# H19R1_Backend.net
KiCad netlist of a schematic drawn in Altium Designer
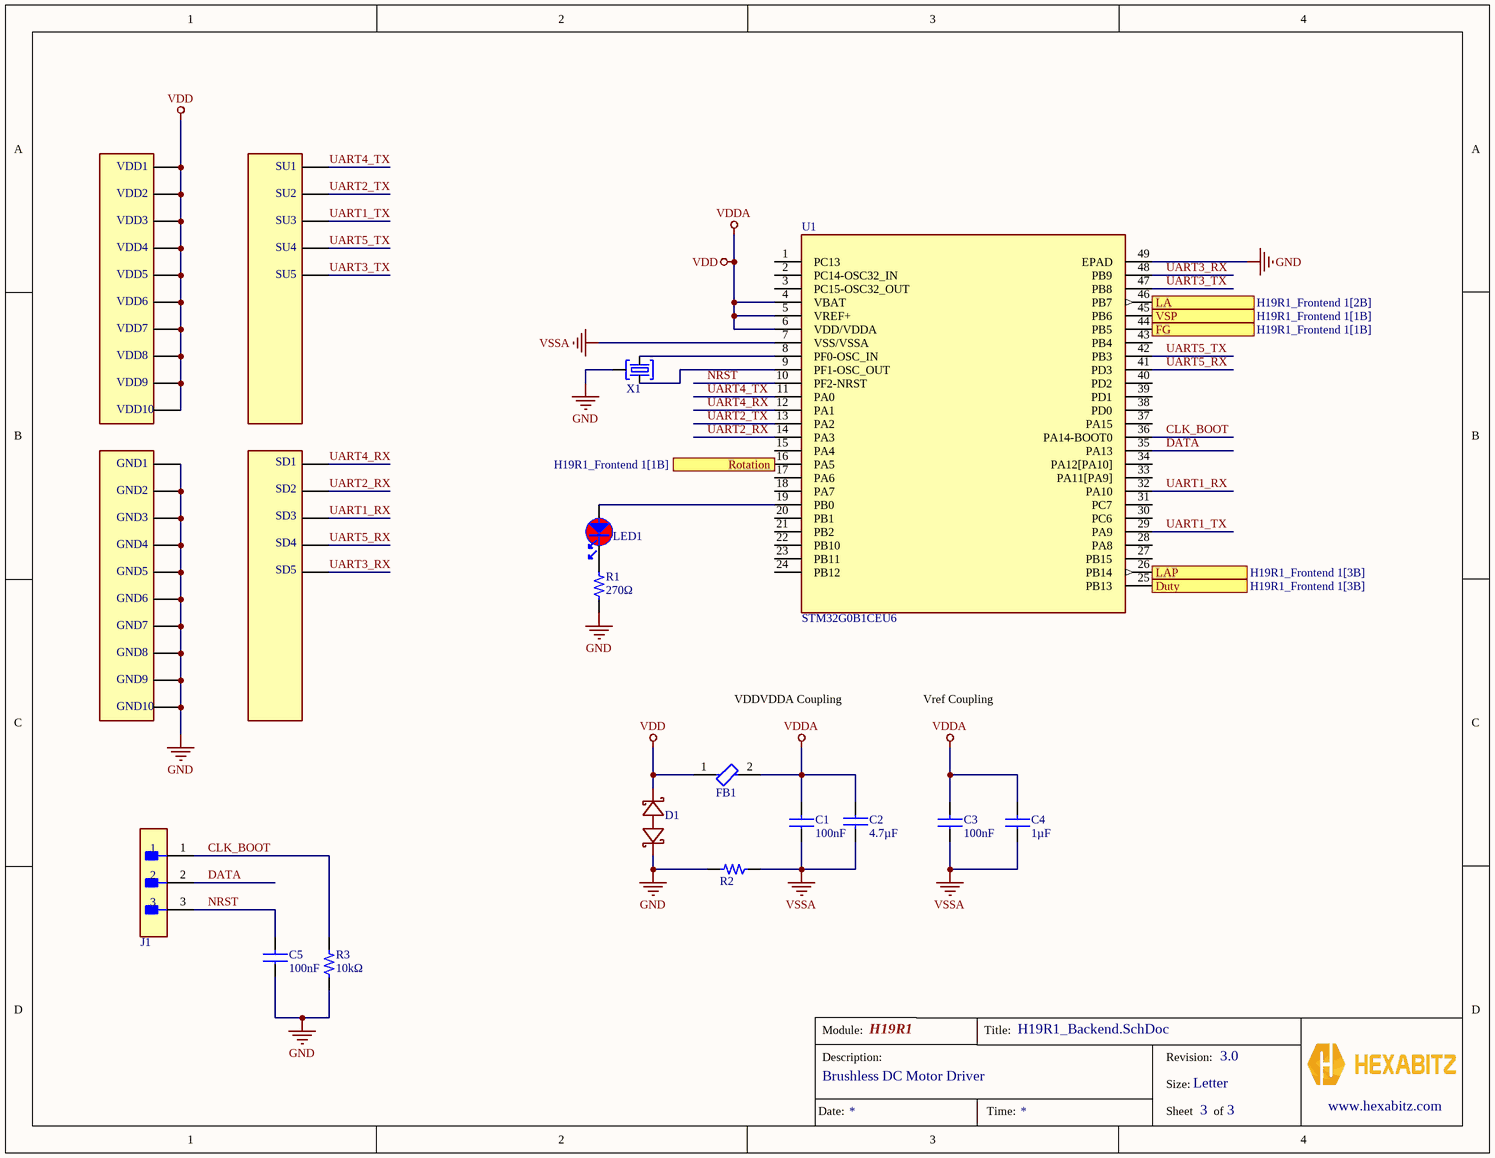
[diagram p0: H19R1_Backend.SchDoc]

(export (version "E")
  (design (tool "Eeschema 10.0.6"))
  (components
    (comp (ref "C1")
      (value "100nF")
      (footprint "C0603")
      (fields
        (field (name "MANUFACTURER") "Samsung Electro-Mechanics")
        (field (name "MANUFACTURER PART NUMBER") "CL10B104KA8NNNC")
        (field (name "TOLERANCE") "10%")
      )
      (libsource (lib "Hexabitz Altium Library") (part "generic Capacitor"))
    )
    (comp (ref "C2")
      (value "4.7µF")
      (footprint "C0805")
      (fields
        (field (name "MANUFACTURER") "Samsung Electro-Mechanics")
        (field (name "MANUFACTURER PART NUMBER") "CL21X475KAQNNNE")
        (field (name "TOLERANCE") "10%")
      )
      (libsource (lib "Hexabitz Altium Library") (part "generic Capacitor"))
    )
    (comp (ref "C3")
      (value "100nF")
      (footprint "C0603")
      (fields
        (field (name "MANUFACTURER") "Samsung Electro-Mechanics")
        (field (name "MANUFACTURER PART NUMBER") "CL10B104KA8NNNC")
        (field (name "TOLERANCE") "10%")
      )
      (libsource (lib "Hexabitz Altium Library") (part "generic Capacitor"))
    )
    (comp (ref "C4")
      (value "1µF")
      (footprint "C0805")
      (description "Ceramic Capacitor, Ceramic, 16V, 10% +Tol, 10% -Tol, X7R, 15% TC, 1uF, Surface Mount, 0805")
      (fields
        (field (name "MANUFACTURER") "Yageo Group")
        (field (name "MANUFACTURER PART NUMBER") "CC0805KKX7R7BB105")
      )
      (libsource (lib "Hexabitz Altium Library") (part "generic Capacitor"))
    )
    (comp (ref "C5")
      (value "100nF")
      (footprint "C0603")
      (fields
        (field (name "MANUFACTURER") "Samsung Electro-Mechanics")
        (field (name "MANUFACTURER PART NUMBER") "CL10B104KA8NNNC")
        (field (name "TOLERANCE") "10%")
      )
      (libsource (lib "Hexabitz Altium Library") (part "generic Capacitor"))
    )
    (comp (ref "D1")
      (value "CDSOD323-T03SC")
      (footprint "SOD2513X114N")
      (description "A 3V, 350W, bi-directional, standard capacitance, SOD323 pkg TVS Diode ¦ Bourns CDSOD323-T03SC")
      (fields (field (name "MANUFACTURER") "Bourns"))
      (libsource (lib "Hexabitz Altium Library") (part "CDSOD323-T03SC"))
    )
    (comp (ref "FB1")
      (value "MMZ1608Y300B")
      (footprint "FP-MMZ1608-0_8-MFG")
      (description "Ferrite Beads 0603 30ohms 1500mA Signal Line AEC-Q200")
      (fields
        (field (name "MANUFACTURER") "TDK")
        (field (name "MANUFACTURER PART NUMBER") "MMZ1608Y300BTD25")
      )
      (libsource (lib "Hexabitz Altium Library") (part "MMZ1608Y300B"))
    )
    (comp (ref "GND1")
      (value "HEXABIT_UART_PORT")
      (footprint "HEXABIT_POWER_PORT_D")
      (libsource (lib "hexabitz_connectors.Library") (part "HEXABIT_POWER_PORT_D"))
    )
    (comp (ref "GND2")
      (value "HEXABIT_UART_PORT")
      (footprint "HEXABIT_POWER_PORT_D")
      (libsource (lib "hexabitz_connectors.Library") (part "HEXABIT_POWER_PORT_D"))
    )
    (comp (ref "GND3")
      (value "HEXABIT_UART_PORT")
      (footprint "HEXABIT_POWER_PORT_D_300R")
      (libsource (lib "hexabitz_connectors.Library") (part "HEXABIT_POWER_PORT_D_300R"))
    )
    (comp (ref "GND4")
      (value "HEXABIT_UART_PORT")
      (footprint "HEXABIT_POWER_PORT_D")
      (libsource (lib "hexabitz_connectors.Library") (part "HEXABIT_POWER_PORT_D"))
    )
    (comp (ref "GND5")
      (value "HEXABIT_UART_PORT")
      (footprint "HEXABIT_POWER_PORT_D")
      (libsource (lib "hexabitz_connectors.Library") (part "HEXABIT_POWER_PORT_D"))
    )
    (comp (ref "GND6")
      (value "HEXABIT_UART_PORT")
      (footprint "HEXABIT_POWER_PORT_D")
      (libsource (lib "hexabitz_connectors.Library") (part "HEXABIT_POWER_PORT_D"))
    )
    (comp (ref "GND7")
      (value "HEXABIT_UART_PORT")
      (footprint "HEXABIT_POWER_PORT_D")
      (libsource (lib "hexabitz_connectors.Library") (part "HEXABIT_POWER_PORT_D"))
    )
    (comp (ref "GND8")
      (value "HEXABIT_UART_PORT")
      (footprint "HEXABIT_POWER_PORT_D_300L")
      (libsource (lib "hexabitz_connectors.Library") (part "HEXABIT_POWER_PORT_D_300L"))
    )
    (comp (ref "GND9")
      (value "HEXABIT_UART_PORT")
      (footprint "HEXABIT_POWER_PORT_D")
      (libsource (lib "hexabitz_connectors.Library") (part "HEXABIT_POWER_PORT_D"))
    )
    (comp (ref "GND10")
      (value "HEXABIT_UART_PORT")
      (footprint "HEXABIT_POWER_PORT_D")
      (libsource (lib "hexabitz_connectors.Library") (part "HEXABIT_POWER_PORT_D"))
    )
    (comp (ref "J1")
      (value "TSW-103-14-G-S")
      (footprint "FP-TSW-103-14-G-S-MFG")
      (description "CONN HEADER VERT 3POS 2.54MM")
      (libsource (lib "Altium Content Vault") (part "cd3439d6ef35ae5d9b27ec4fdd3e828"))
    )
    (comp (ref "LED1")
      (value "VLMS1300-GS08")
      (footprint "FP-6_541-5092_01-4-MFG")
      (description "LED Uni-Color Super Red 639nm 2-Pin Chip 0603(1608Metric) T/R")
      (fields (field (name "MANUFACTURER") "Vishay Semiconductors"))
      (libsource (lib "Hexabitz Altium Library") (part "VLMS1300-GS08"))
    )
    (comp (ref "R1")
      (value "270Ω")
      (footprint "R0603")
      (description "Res Thick Film 0603 270 Ohm 5% 0.1W(1/10W) ±200ppm/C Pad SMD Automotive T/R")
      (fields
        (field (name "MANUFACTURER") "Panasonic")
        (field (name "MANUFACTURER PART NUMBER") "ERJ-3GEYJ271V")
      )
      (libsource (lib "") (part "generic Resistor_2"))
    )
    (comp (ref "R2")
      (value "Manufacturer Part Number")
      (footprint "R0603")
      (libsource (lib "Hexabitz Altium Library") (part "generic Resistor"))
    )
    (comp (ref "R3")
      (value "10kΩ")
      (footprint "R0603")
      (description "100mW Thick Film Resistors ±100ppm/℃ ±1% 10kΩ 0603 Chip Resistor - Surface Mount ROHS")
      (fields
        (field (name "MANUFACTURER") "Yageo Group")
        (field (name "MANUFACTURER PART NUMBER") "RC0603FR-0710KL")
      )
      (libsource (lib "") (part "generic Resistor_1"))
    )
    (comp (ref "SD1")
      (value "HEXABIT_UART_PORT")
      (footprint "HEXABIT_UART_PORT_D")
      (libsource (lib "hexabitz_connectors.Library") (part "HEXABIT_UART_PORT_D"))
    )
    (comp (ref "SD2")
      (value "HEXABIT_UART_PORT")
      (footprint "HEXABIT_UART_PORT_D")
      (libsource (lib "hexabitz_connectors.Library") (part "HEXABIT_UART_PORT_D"))
    )
    (comp (ref "SD3")
      (value "HEXABIT_UART_PORT")
      (footprint "HEXABIT_UART_PORT_D")
      (libsource (lib "hexabitz_connectors.Library") (part "HEXABIT_UART_PORT_D"))
    )
    (comp (ref "SD4")
      (value "HEXABIT_UART_PORT")
      (footprint "HEXABIT_UART_PORT_D")
      (libsource (lib "hexabitz_connectors.Library") (part "HEXABIT_UART_PORT_D"))
    )
    (comp (ref "SD5")
      (value "HEXABIT_UART_PORT")
      (footprint "HEXABIT_UART_PORT_D")
      (libsource (lib "hexabitz_connectors.Library") (part "HEXABIT_UART_PORT_D"))
    )
    (comp (ref "SU1")
      (value "HEXABIT_UART_PORT")
      (footprint "HEXABIT_UART_PORT_U")
      (libsource (lib "hexabitz_connectors.Library") (part "HEXABIT_UART_PORT_U"))
    )
    (comp (ref "SU2")
      (value "HEXABIT_UART_PORT")
      (footprint "HEXABIT_UART_PORT_U")
      (libsource (lib "hexabitz_connectors.Library") (part "HEXABIT_UART_PORT_U"))
    )
    (comp (ref "SU3")
      (value "HEXABIT_UART_PORT")
      (footprint "HEXABIT_UART_PORT_U")
      (libsource (lib "hexabitz_connectors.Library") (part "HEXABIT_UART_PORT_U"))
    )
    (comp (ref "SU4")
      (value "HEXABIT_UART_PORT")
      (footprint "HEXABIT_UART_PORT_U")
      (libsource (lib "hexabitz_connectors.Library") (part "HEXABIT_UART_PORT_U"))
    )
    (comp (ref "SU5")
      (value "HEXABIT_UART_PORT")
      (footprint "HEXABIT_UART_PORT_U")
      (libsource (lib "hexabitz_connectors.Library") (part "HEXABIT_UART_PORT_U"))
    )
    (comp (ref "U1")
      (value "STM32G0B1CEU6")
      (footprint "QFN50P700X700X65-49N-D")
      (description "MCU 32-bit ARM Cortex M0+ RISC 512KB Flash 1.8V/2.5V/3.3V 48-Pin UFQFPN EP Tray")
      (fields
        (field (name "MANUFACTURER") "STMicroelectronics")
        (field (name "MANUFACTURER PART NUMBER") "STM32G0B1CEU6")
      )
      (libsource (lib "Hexabitz Altium Library") (part "STM32G0B1CEU6"))
    )
    (comp (ref "VDD1")
      (value "HEXABIT_UART_PORT")
      (footprint "HEXABIT_POWER_PORT_U")
      (libsource (lib "hexabitz_connectors.Library") (part "HEXABIT_POWER_PORT_U"))
    )
    (comp (ref "VDD2")
      (value "HEXABIT_UART_PORT")
      (footprint "HEXABIT_POWER_PORT_U")
      (libsource (lib "hexabitz_connectors.Library") (part "HEXABIT_POWER_PORT_U"))
    )
    (comp (ref "VDD3")
      (value "HEXABIT_UART_PORT")
      (footprint "HEXABIT_POWER_PORT_U_300R")
      (libsource (lib "hexabitz_connectors.Library") (part "HEXABIT_POWER_PORT_U_300R"))
    )
    (comp (ref "VDD4")
      (value "HEXABIT_UART_PORT")
      (footprint "HEXABIT_POWER_PORT_U")
      (libsource (lib "hexabitz_connectors.Library") (part "HEXABIT_POWER_PORT_U"))
    )
    (comp (ref "VDD5")
      (value "HEXABIT_UART_PORT")
      (footprint "HEXABIT_POWER_PORT_U")
      (libsource (lib "hexabitz_connectors.Library") (part "HEXABIT_POWER_PORT_U"))
    )
    (comp (ref "VDD6")
      (value "HEXABIT_UART_PORT")
      (footprint "HEXABIT_POWER_PORT_U")
      (libsource (lib "hexabitz_connectors.Library") (part "HEXABIT_POWER_PORT_U"))
    )
    (comp (ref "VDD7")
      (value "HEXABIT_UART_PORT")
      (footprint "HEXABIT_POWER_PORT_U")
      (libsource (lib "hexabitz_connectors.Library") (part "HEXABIT_POWER_PORT_U"))
    )
    (comp (ref "VDD8")
      (value "HEXABIT_UART_PORT")
      (footprint "HEXABIT_POWER_PORT_U_300L")
      (libsource (lib "hexabitz_connectors.Library") (part "HEXABIT_POWER_PORT_U_300L"))
    )
    (comp (ref "VDD9")
      (value "HEXABIT_UART_PORT")
      (footprint "HEXABIT_POWER_PORT_U")
      (libsource (lib "hexabitz_connectors.Library") (part "HEXABIT_POWER_PORT_U"))
    )
    (comp (ref "VDD10")
      (value "HEXABIT_UART_PORT")
      (footprint "HEXABIT_POWER_PORT_U")
      (libsource (lib "hexabitz_connectors.Library") (part "HEXABIT_POWER_PORT_U"))
    )
    (comp (ref "X1")
      (value "CSTCE8M00G52Z-R0")
      (footprint "XTALL_CSTCE8M00G52")
      (description "Ceramic Resonator 8MHz ±0.5% (Tol) ±0.2% (Stability) 10pF 40Ohm 3-Pin CSMD T/R")
      (fields (field (name "MANUFACTURER") "Murata") (field (name "TOLERANCE") "0.5%"))
      (libsource (lib "Hexabitz Altium Library") (part "CSTCE8M00G52Z-R0"))
    )
  )
  (nets
    (net (code "1") (name "/CLK_BOOT") (class "Default")
      (node (ref "J1") (pin "1") (pinfunction "1_1") (pintype "passive"))
      (node (ref "R3") (pin "1") (pinfunction "1_1") (pintype "passive"))
      (node (ref "U1") (pin "36") (pinfunction "PA14-BOOT0_36") (pintype "passive"))
    )
    (net (code "2") (name "/DATA") (class "Default")
      (node (ref "J1") (pin "2") (pinfunction "2_2") (pintype "passive"))
      (node (ref "U1") (pin "35") (pinfunction "PA13_35") (pintype "passive"))
    )
    (net (code "3") (name "/Duty") (class "Default")
      (node (ref "U1") (pin "25") (pinfunction "PB13_25") (pintype "passive"))
    )
    (net (code "4") (name "/FG") (class "Default")
      (node (ref "U1") (pin "44") (pinfunction "PB5_44") (pintype "passive"))
    )
    (net (code "5") (name "/LA") (class "Default")
      (node (ref "U1") (pin "46") (pinfunction "PB7_46") (pintype "output"))
    )
    (net (code "6") (name "/LAP") (class "Default")
      (node (ref "U1") (pin "26") (pinfunction "PB14_26") (pintype "output"))
    )
    (net (code "7") (name "/NRST") (class "Default")
      (node (ref "C5") (pin "2") (pinfunction "2_2") (pintype "passive"))
      (node (ref "J1") (pin "3") (pinfunction "3_3") (pintype "passive"))
      (node (ref "U1") (pin "10") (pinfunction "PF2-NRST_10") (pintype "passive"))
    )
    (net (code "8") (name "/Rotation") (class "Default")
      (node (ref "U1") (pin "16") (pinfunction "PA5_16") (pintype "passive"))
    )
    (net (code "9") (name "/UART1_RX") (class "Default")
      (node (ref "SD3") (pin "UART_D") (pinfunction "UART_D_UART_D") (pintype "passive"))
      (node (ref "U1") (pin "32") (pinfunction "PA10_32") (pintype "passive"))
    )
    (net (code "10") (name "/UART1_TX") (class "Default")
      (node (ref "SU3") (pin "UART_U") (pinfunction "UART_U_UART_U") (pintype "passive"))
      (node (ref "U1") (pin "29") (pinfunction "PA9_29") (pintype "passive"))
    )
    (net (code "11") (name "/UART2_RX") (class "Default")
      (node (ref "SD2") (pin "UART_D") (pinfunction "UART_D_UART_D") (pintype "passive"))
      (node (ref "U1") (pin "14") (pinfunction "PA3_14") (pintype "passive"))
    )
    (net (code "12") (name "/UART2_TX") (class "Default")
      (node (ref "SU2") (pin "UART_U") (pinfunction "UART_U_UART_U") (pintype "passive"))
      (node (ref "U1") (pin "13") (pinfunction "PA2_13") (pintype "passive"))
    )
    (net (code "13") (name "/UART3_RX") (class "Default")
      (node (ref "SD5") (pin "UART_D") (pinfunction "UART_D_UART_D") (pintype "passive"))
      (node (ref "U1") (pin "48") (pinfunction "PB9_48") (pintype "passive"))
    )
    (net (code "14") (name "/UART3_TX") (class "Default")
      (node (ref "SU5") (pin "UART_U") (pinfunction "UART_U_UART_U") (pintype "passive"))
      (node (ref "U1") (pin "47") (pinfunction "PB8_47") (pintype "passive"))
    )
    (net (code "15") (name "/UART4_RX") (class "Default")
      (node (ref "SD1") (pin "UART_D") (pinfunction "UART_D_UART_D") (pintype "passive"))
      (node (ref "U1") (pin "12") (pinfunction "PA1_12") (pintype "passive"))
    )
    (net (code "16") (name "/UART4_TX") (class "Default")
      (node (ref "SU1") (pin "UART_U") (pinfunction "UART_U_UART_U") (pintype "passive"))
      (node (ref "U1") (pin "11") (pinfunction "PA0_11") (pintype "passive"))
    )
    (net (code "17") (name "/UART5_RX") (class "Default")
      (node (ref "SD4") (pin "UART_D") (pinfunction "UART_D_UART_D") (pintype "passive"))
      (node (ref "U1") (pin "41") (pinfunction "PD3_41") (pintype "passive"))
    )
    (net (code "18") (name "/UART5_TX") (class "Default")
      (node (ref "SU4") (pin "UART_U") (pinfunction "UART_U_UART_U") (pintype "passive"))
      (node (ref "U1") (pin "42") (pinfunction "PB3_42") (pintype "passive"))
    )
    (net (code "19") (name "/VSP") (class "Default")
      (node (ref "U1") (pin "45") (pinfunction "PB6_45") (pintype "passive"))
    )
    (net (code "20") (name "GND") (class "Default")
      (node (ref "C5") (pin "1") (pinfunction "1_1") (pintype "passive"))
      (node (ref "D1") (pin "1") (pinfunction "A_1") (pintype "passive"))
      (node (ref "GND1") (pin "Pwr_D") (pinfunction "Pwr_D_Pwr_D") (pintype "passive"))
      (node (ref "GND10") (pin "Pwr_D") (pinfunction "Pwr_D_Pwr_D") (pintype "passive"))
      (node (ref "GND2") (pin "Pwr_D") (pinfunction "Pwr_D_Pwr_D") (pintype "passive"))
      (node (ref "GND3") (pin "Pwr_D") (pinfunction "Pwr_D_Pwr_D") (pintype "passive"))
      (node (ref "GND4") (pin "Pwr_D") (pinfunction "Pwr_D_Pwr_D") (pintype "passive"))
      (node (ref "GND5") (pin "Pwr_D") (pinfunction "Pwr_D_Pwr_D") (pintype "passive"))
      (node (ref "GND6") (pin "Pwr_D") (pinfunction "Pwr_D_Pwr_D") (pintype "passive"))
      (node (ref "GND7") (pin "Pwr_D") (pinfunction "Pwr_D_Pwr_D") (pintype "passive"))
      (node (ref "GND8") (pin "Pwr_D") (pinfunction "Pwr_D_Pwr_D") (pintype "passive"))
      (node (ref "GND9") (pin "Pwr_D") (pinfunction "Pwr_D_Pwr_D") (pintype "passive"))
      (node (ref "R1") (pin "1") (pinfunction "1_1") (pintype "passive"))
      (node (ref "R2") (pin "1") (pinfunction "1_1") (pintype "passive"))
      (node (ref "R3") (pin "2") (pinfunction "2_2") (pintype "passive"))
      (node (ref "U1") (pin "49") (pinfunction "EPAD_49") (pintype "passive"))
      (node (ref "X1") (pin "P$2") (pinfunction "2_P$2") (pintype "passive"))
    )
    (net (code "21") (name "Net-(LED1-Pad1)") (class "Default")
      (node (ref "LED1") (pin "1") (pintype "passive"))
      (node (ref "R1") (pin "2") (pinfunction "2_2") (pintype "passive"))
    )
    (net (code "22") (name "Net-(U1-PB0)") (class "Default")
      (node (ref "LED1") (pin "2") (pintype "passive"))
      (node (ref "U1") (pin "19") (pinfunction "PB0_19") (pintype "passive"))
    )
    (net (code "23") (name "Net-(U1-PF0-OSC_IN)") (class "Default")
      (node (ref "U1") (pin "8") (pinfunction "PF0-OSC_IN_8") (pintype "passive"))
      (node (ref "X1") (pin "P$3") (pinfunction "3_P$3") (pintype "passive"))
    )
    (net (code "24") (name "Net-(U1-PF1-OSC_OUT)") (class "Default")
      (node (ref "U1") (pin "9") (pinfunction "PF1-OSC_OUT_9") (pintype "passive"))
      (node (ref "X1") (pin "P$1") (pinfunction "1_P$1") (pintype "passive"))
    )
    (net (code "25") (name "VDD") (class "Default")
      (node (ref "C1") (pin "2") (pinfunction "2_2") (pintype "passive"))
      (node (ref "C2") (pin "1") (pinfunction "1_1") (pintype "passive"))
      (node (ref "C3") (pin "2") (pinfunction "2_2") (pintype "passive"))
      (node (ref "C4") (pin "2") (pinfunction "2_2") (pintype "passive"))
      (node (ref "D1") (pin "2") (pinfunction "C_2") (pintype "passive"))
      (node (ref "FB1") (pin "1") (pinfunction "1_1") (pintype "passive"))
      (node (ref "FB1") (pin "2") (pinfunction "2_2") (pintype "passive"))
      (node (ref "U1") (pin "4") (pinfunction "VBAT_4") (pintype "passive"))
      (node (ref "U1") (pin "5") (pinfunction "VREF+_5") (pintype "passive"))
      (node (ref "U1") (pin "6") (pinfunction "VDD/VDDA_6") (pintype "passive"))
      (node (ref "VDD1") (pin "Pwr_U") (pinfunction "Pwr_U_Pwr_U") (pintype "passive"))
      (node (ref "VDD10") (pin "Pwr_U") (pinfunction "Pwr_U_Pwr_U") (pintype "passive"))
      (node (ref "VDD2") (pin "Pwr_U") (pinfunction "Pwr_U_Pwr_U") (pintype "passive"))
      (node (ref "VDD3") (pin "Pwr_U") (pinfunction "Pwr_U_Pwr_U") (pintype "passive"))
      (node (ref "VDD4") (pin "Pwr_U") (pinfunction "Pwr_U_Pwr_U") (pintype "passive"))
      (node (ref "VDD5") (pin "Pwr_U") (pinfunction "Pwr_U_Pwr_U") (pintype "passive"))
      (node (ref "VDD6") (pin "Pwr_U") (pinfunction "Pwr_U_Pwr_U") (pintype "passive"))
      (node (ref "VDD7") (pin "Pwr_U") (pinfunction "Pwr_U_Pwr_U") (pintype "passive"))
      (node (ref "VDD8") (pin "Pwr_U") (pinfunction "Pwr_U_Pwr_U") (pintype "passive"))
      (node (ref "VDD9") (pin "Pwr_U") (pinfunction "Pwr_U_Pwr_U") (pintype "passive"))
    )
    (net (code "26") (name "VSSA") (class "Default")
      (node (ref "C1") (pin "1") (pinfunction "1_1") (pintype "passive"))
      (node (ref "C2") (pin "2") (pinfunction "2_2") (pintype "passive"))
      (node (ref "C3") (pin "1") (pinfunction "1_1") (pintype "passive"))
      (node (ref "C4") (pin "1") (pinfunction "1_1") (pintype "passive"))
      (node (ref "R2") (pin "2") (pinfunction "2_2") (pintype "passive"))
      (node (ref "U1") (pin "7") (pinfunction "VSS/VSSA_7") (pintype "passive"))
    )
    (net (code "27") (name "unconnected-(U1-PA4-Pad15)") (class "Default")
      (node (ref "U1") (pin "15") (pinfunction "PA4_15") (pintype "passive"))
    )
    (net (code "28") (name "unconnected-(U1-PA6-Pad17)") (class "Default")
      (node (ref "U1") (pin "17") (pinfunction "PA6_17") (pintype "passive"))
    )
    (net (code "29") (name "unconnected-(U1-PA7-Pad18)") (class "Default")
      (node (ref "U1") (pin "18") (pinfunction "PA7_18") (pintype "passive"))
    )
    (net (code "30") (name "unconnected-(U1-PA8-Pad28)") (class "Default")
      (node (ref "U1") (pin "28") (pinfunction "PA8_28") (pintype "passive"))
    )
    (net (code "31") (name "unconnected-(U1-PA11[PA9]-Pad33)") (class "Default")
      (node (ref "U1") (pin "33") (pinfunction "PA11[PA9]_33") (pintype "passive"))
    )
    (net (code "32") (name "unconnected-(U1-PA12[PA10]-Pad34)") (class "Default")
      (node (ref "U1") (pin "34") (pinfunction "PA12[PA10]_34") (pintype "passive"))
    )
    (net (code "33") (name "unconnected-(U1-PA15-Pad37)") (class "Default")
      (node (ref "U1") (pin "37") (pinfunction "PA15_37") (pintype "passive"))
    )
    (net (code "34") (name "unconnected-(U1-PB1-Pad20)") (class "Default")
      (node (ref "U1") (pin "20") (pinfunction "PB1_20") (pintype "passive"))
    )
    (net (code "35") (name "unconnected-(U1-PB2-Pad21)") (class "Default")
      (node (ref "U1") (pin "21") (pinfunction "PB2_21") (pintype "passive"))
    )
    (net (code "36") (name "unconnected-(U1-PB4-Pad43)") (class "Default")
      (node (ref "U1") (pin "43") (pinfunction "PB4_43") (pintype "passive"))
    )
    (net (code "37") (name "unconnected-(U1-PB10-Pad22)") (class "Default")
      (node (ref "U1") (pin "22") (pinfunction "PB10_22") (pintype "passive"))
    )
    (net (code "38") (name "unconnected-(U1-PB11-Pad23)") (class "Default")
      (node (ref "U1") (pin "23") (pinfunction "PB11_23") (pintype "passive"))
    )
    (net (code "39") (name "unconnected-(U1-PB12-Pad24)") (class "Default")
      (node (ref "U1") (pin "24") (pinfunction "PB12_24") (pintype "passive"))
    )
    (net (code "40") (name "unconnected-(U1-PB15-Pad27)") (class "Default")
      (node (ref "U1") (pin "27") (pinfunction "PB15_27") (pintype "passive"))
    )
    (net (code "41") (name "unconnected-(U1-PC6-Pad30)") (class "Default")
      (node (ref "U1") (pin "30") (pinfunction "PC6_30") (pintype "passive"))
    )
    (net (code "42") (name "unconnected-(U1-PC7-Pad31)") (class "Default")
      (node (ref "U1") (pin "31") (pinfunction "PC7_31") (pintype "passive"))
    )
    (net (code "43") (name "unconnected-(U1-PC13-Pad1)") (class "Default")
      (node (ref "U1") (pin "1") (pinfunction "PC13_1") (pintype "passive"))
    )
    (net (code "44") (name "unconnected-(U1-PC14-OSC32_IN-Pad2)") (class "Default")
      (node (ref "U1") (pin "2") (pinfunction "PC14-OSC32_IN_2") (pintype "passive"))
    )
    (net (code "45") (name "unconnected-(U1-PC15-OSC32_OUT-Pad3)") (class "Default")
      (node (ref "U1") (pin "3") (pinfunction "PC15-OSC32_OUT_3") (pintype "passive"))
    )
    (net (code "46") (name "unconnected-(U1-PD0-Pad38)") (class "Default")
      (node (ref "U1") (pin "38") (pinfunction "PD0_38") (pintype "passive"))
    )
    (net (code "47") (name "unconnected-(U1-PD1-Pad39)") (class "Default")
      (node (ref "U1") (pin "39") (pinfunction "PD1_39") (pintype "passive"))
    )
    (net (code "48") (name "unconnected-(U1-PD2-Pad40)") (class "Default")
      (node (ref "U1") (pin "40") (pinfunction "PD2_40") (pintype "passive"))
    )
  )
)
